# SCH_ZX_WiFi_2022-08-20.net
KiCad netlist of a schematic drawn in EasyEDA
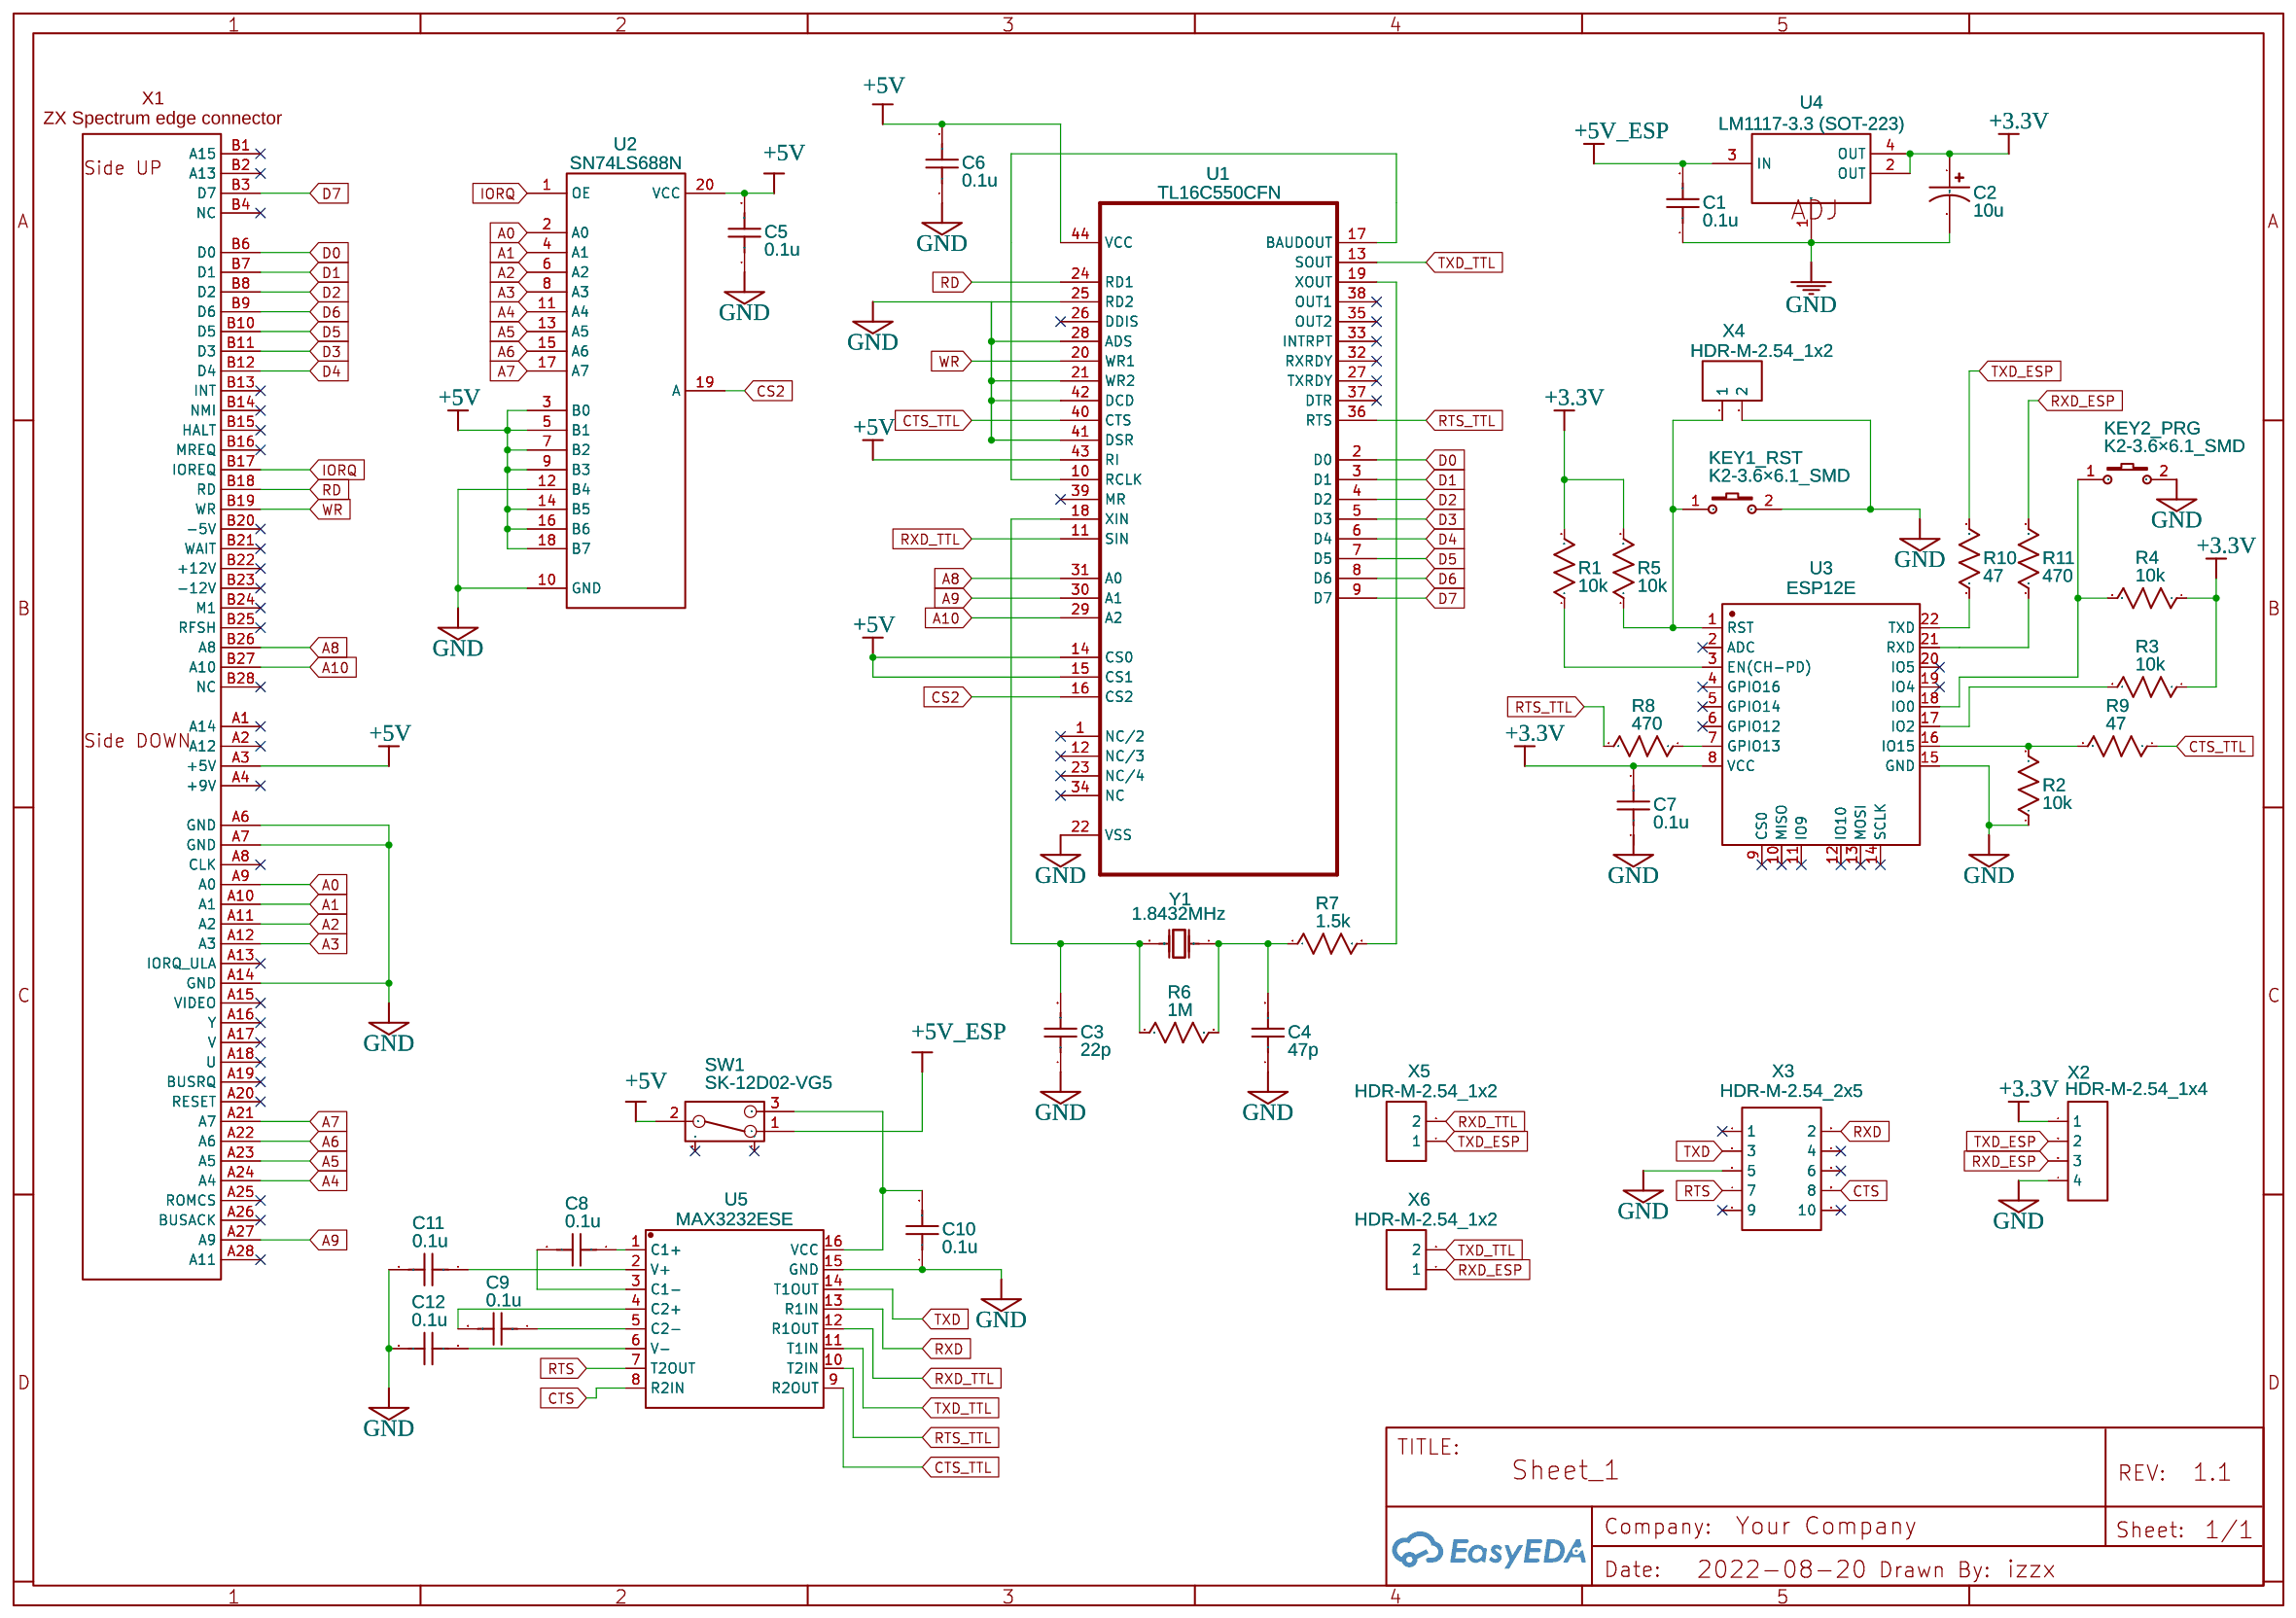
[diagram p0: schematic sheet]

(export (version "E")
  (design (tool "Eeschema 10.0.6"))
  (components
    (comp (ref "C1") (value "0.1u") (libsource (lib "") (part "C_0805_US")))
    (comp (ref "C2") (value "10u") (libsource (lib "") (part "C_Tan_SMD_A_US")))
    (comp (ref "C3") (value "22p") (libsource (lib "") (part "C_0805_US")))
    (comp (ref "C4") (value "47p") (libsource (lib "") (part "C_0805_US")))
    (comp (ref "C5") (value "0.1u") (libsource (lib "") (part "C_0805_US")))
    (comp (ref "C6") (value "0.1u") (libsource (lib "") (part "C_0805_US")))
    (comp (ref "C7") (value "0.1u") (libsource (lib "") (part "C_0805_US")))
    (comp (ref "C8") (value "0.1u") (libsource (lib "") (part "C_0805_US_1")))
    (comp (ref "C9") (value "0.1u") (libsource (lib "") (part "C_0805_US_1")))
    (comp (ref "C10") (value "0.1u") (libsource (lib "") (part "C_0805_US")))
    (comp (ref "C11") (value "0.1u") (libsource (lib "") (part "C_0805_US_1")))
    (comp (ref "C12") (value "0.1u") (libsource (lib "") (part "C_0805_US_1")))
    (comp (ref "KEY1_RST")
      (value "K2-3.6×6.1_SMD")
      (fields
        (field (name "BOM_Manufacturer Part") "K2-1107ST-A4SW-06")
        (field (name "BOM_Supplier Part") "C118141")
      )
      (libsource (lib "") (part "K2-3.6×6.1_SMD_1"))
    )
    (comp (ref "KEY2_PRG")
      (value "K2-3.6×6.1_SMD")
      (fields
        (field (name "BOM_Manufacturer Part") "K2-1107ST-A4SW-06")
        (field (name "BOM_Supplier Part") "C118141")
      )
      (libsource (lib "") (part "K2-3.6×6.1_SMD"))
    )
    (comp (ref "R1") (value "10k") (libsource (lib "") (part "R_0805_US_1")))
    (comp (ref "R2") (value "10k") (libsource (lib "") (part "R_0805_US_1")))
    (comp (ref "R3") (value "10k") (libsource (lib "") (part "R_0805_US_2")))
    (comp (ref "R4") (value "10k") (libsource (lib "") (part "R_0805_US_2")))
    (comp (ref "R5") (value "10k") (libsource (lib "") (part "R_0805_US_1")))
    (comp (ref "R6") (value "1M") (libsource (lib "") (part "R_0805_US")))
    (comp (ref "R7") (value "1.5k") (libsource (lib "") (part "R_0805_US")))
    (comp (ref "R8") (value "470") (libsource (lib "") (part "R_0805_US_2")))
    (comp (ref "R9") (value "47") (libsource (lib "") (part "R_0805_US_2")))
    (comp (ref "R10") (value "47") (libsource (lib "") (part "R_0805_US_1")))
    (comp (ref "R11") (value "470") (libsource (lib "") (part "R_0805_US_1")))
    (comp (ref "SW1")
      (value "SK-12D02-VG5")
      (fields (field (name "BOM_Supplier Part") "C136722"))
      (libsource (lib "") (part "SK-12D02-VG5"))
    )
    (comp (ref "U1") (value "TL16C550CFN") (libsource (lib "") (part "TL16C550CFN")))
    (comp (ref "U2") (value "SN74LS688N") (libsource (lib "") (part "SN74LS688N")))
    (comp (ref "U3") (value "ESP12E") (libsource (lib "") (part "ESP12E/F")))
    (comp (ref "U4")
      (value "LM1117-3.3 (SOT-223)")
      (fields
        (field (name "BOM_Manufacturer Part") "LM317G-AA3-R")
        (field (name "BOM_Supplier Part") "C19651")
      )
      (libsource (lib "") (part "LM317(SOT-223)"))
    )
    (comp (ref "U5")
      (value "MAX3232ESE")
      (fields (field (name "BOM_Supplier Part") "C2904738"))
      (libsource (lib "") (part "MAX3232ESE"))
    )
    (comp (ref "X1") (value "ZX SPECTRUM CONNECTOR") (libsource (lib "") (part "ZX SPECTRUM CONNECTOR")))
    (comp (ref "X2")
      (value "HDR-M-2.54_1x4")
      (fields (field (name "BOM_Supplier Part") "C124378"))
      (libsource (lib "") (part "HDR-M-2.54_1x4"))
    )
    (comp (ref "X3")
      (value "HDR-M-2.54_2x5")
      (fields (field (name "BOM_Supplier Part") "C178292"))
      (libsource (lib "") (part "HDR-M-2.54_2x5"))
    )
    (comp (ref "X4")
      (value "HDR-M-2.54_1x2")
      (fields (field (name "BOM_Supplier Part") "C124375"))
      (libsource (lib "") (part "HDR-M-2.54_1x2_1"))
    )
    (comp (ref "X5")
      (value "HDR-M-2.54_1x2")
      (fields (field (name "BOM_Supplier Part") "C124375"))
      (libsource (lib "") (part "HDR-M-2.54_1x2"))
    )
    (comp (ref "X6")
      (value "HDR-M-2.54_1x2")
      (fields (field (name "BOM_Supplier Part") "C124375"))
      (libsource (lib "") (part "HDR-M-2.54_1x2"))
    )
    (comp (ref "Y1")
      (value "1.8432MHz")
      (fields
        (field (name "BOM_Manufacturer Part") "X49UD3579MSD2SC")
        (field (name "BOM_Supplier Part") "C36564")
      )
      (libsource (lib "") (part "X49UD3579MSD2SC"))
    )
  )
  (nets
    (net (code "1") (name "+3.3V") (class "Default")
      (node (ref "C2") (pin "1") (pinfunction "1_1") (pintype "unspecified"))
      (node (ref "C7") (pin "2") (pinfunction "2_2") (pintype "unspecified"))
      (node (ref "R1") (pin "2") (pinfunction "2_2") (pintype "unspecified"))
      (node (ref "R3") (pin "1") (pinfunction "1_1") (pintype "unspecified"))
      (node (ref "R4") (pin "1") (pinfunction "1_1") (pintype "unspecified"))
      (node (ref "R5") (pin "2") (pinfunction "2_2") (pintype "unspecified"))
      (node (ref "U3") (pin "8") (pinfunction "VCC_8") (pintype "unspecified"))
      (node (ref "U4") (pin "2") (pinfunction "OUT_2") (pintype "passive"))
      (node (ref "U4") (pin "4") (pinfunction "OUT_4") (pintype "passive"))
      (node (ref "X2") (pin "1") (pinfunction "1_1") (pintype "unspecified"))
    )
    (net (code "2") (name "+5V") (class "Default")
      (node (ref "C5") (pin "2") (pinfunction "2_2") (pintype "unspecified"))
      (node (ref "C6") (pin "2") (pinfunction "2_2") (pintype "unspecified"))
      (node (ref "SW1") (pin "2") (pinfunction "2_2") (pintype "unspecified"))
      (node (ref "U1") (pin "14") (pinfunction "CS0_14") (pintype "input"))
      (node (ref "U1") (pin "15") (pinfunction "CS1_15") (pintype "input"))
      (node (ref "U1") (pin "43") (pinfunction "RI_43") (pintype "input"))
      (node (ref "U1") (pin "44") (pinfunction "VCC_44") (pintype "passive"))
      (node (ref "U2") (pin "14") (pinfunction "B5_14") (pintype "unspecified"))
      (node (ref "U2") (pin "16") (pinfunction "B6_16") (pintype "unspecified"))
      (node (ref "U2") (pin "18") (pinfunction "B7_18") (pintype "unspecified"))
      (node (ref "U2") (pin "20") (pinfunction "VCC_20") (pintype "passive"))
      (node (ref "U2") (pin "3") (pinfunction "B0_3") (pintype "unspecified"))
      (node (ref "U2") (pin "5") (pinfunction "B1_5") (pintype "unspecified"))
      (node (ref "U2") (pin "7") (pinfunction "B2_7") (pintype "unspecified"))
      (node (ref "U2") (pin "9") (pinfunction "B3_9") (pintype "unspecified"))
      (node (ref "X1") (pin "A3") (pinfunction "+5V_A3") (pintype "unspecified"))
    )
    (net (code "3") (name "+5V_ESP") (class "Default")
      (node (ref "C1") (pin "2") (pinfunction "2_2") (pintype "unspecified"))
      (node (ref "SW1") (pin "1") (pinfunction "1_1") (pintype "unspecified"))
      (node (ref "U4") (pin "3") (pinfunction "IN_3") (pintype "passive"))
    )
    (net (code "4") (name "A0") (class "Default")
      (node (ref "U2") (pin "2") (pinfunction "A0_2") (pintype "unspecified"))
      (node (ref "X1") (pin "A9") (pinfunction "A0_A9") (pintype "unspecified"))
    )
    (net (code "5") (name "A1") (class "Default")
      (node (ref "U2") (pin "4") (pinfunction "A1_4") (pintype "unspecified"))
      (node (ref "X1") (pin "A10") (pinfunction "A1_A10") (pintype "unspecified"))
    )
    (net (code "6") (name "A2") (class "Default")
      (node (ref "U2") (pin "6") (pinfunction "A2_6") (pintype "unspecified"))
      (node (ref "X1") (pin "A11") (pinfunction "A2_A11") (pintype "unspecified"))
    )
    (net (code "7") (name "A3") (class "Default")
      (node (ref "U2") (pin "8") (pinfunction "A3_8") (pintype "unspecified"))
      (node (ref "X1") (pin "A12") (pinfunction "A3_A12") (pintype "unspecified"))
    )
    (net (code "8") (name "A4") (class "Default")
      (node (ref "U2") (pin "11") (pinfunction "A4_11") (pintype "unspecified"))
      (node (ref "X1") (pin "A24") (pinfunction "A4_A24") (pintype "unspecified"))
    )
    (net (code "9") (name "A5") (class "Default")
      (node (ref "U2") (pin "13") (pinfunction "A5_13") (pintype "unspecified"))
      (node (ref "X1") (pin "A23") (pinfunction "A5_A23") (pintype "unspecified"))
    )
    (net (code "10") (name "A6") (class "Default")
      (node (ref "U2") (pin "15") (pinfunction "A6_15") (pintype "unspecified"))
      (node (ref "X1") (pin "A22") (pinfunction "A6_A22") (pintype "unspecified"))
    )
    (net (code "11") (name "A7") (class "Default")
      (node (ref "U2") (pin "17") (pinfunction "A7_17") (pintype "unspecified"))
      (node (ref "X1") (pin "A21") (pinfunction "A7_A21") (pintype "unspecified"))
    )
    (net (code "12") (name "A8") (class "Default")
      (node (ref "U1") (pin "31") (pinfunction "A0_31") (pintype "input"))
      (node (ref "X1") (pin "B26") (pinfunction "A8_B26") (pintype "unspecified"))
    )
    (net (code "13") (name "A9") (class "Default")
      (node (ref "U1") (pin "30") (pinfunction "A1_30") (pintype "input"))
      (node (ref "X1") (pin "A27") (pinfunction "A9_A27") (pintype "unspecified"))
    )
    (net (code "14") (name "A10") (class "Default")
      (node (ref "U1") (pin "29") (pinfunction "A2_29") (pintype "input"))
      (node (ref "X1") (pin "B27") (pinfunction "A10_B27") (pintype "unspecified"))
    )
    (net (code "15") (name "CS2") (class "Default")
      (node (ref "U1") (pin "16") (pinfunction "CS2_16") (pintype "input"))
      (node (ref "U2") (pin "19") (pinfunction "A_19") (pintype "output"))
    )
    (net (code "16") (name "CTS") (class "Default")
      (node (ref "U5") (pin "8") (pinfunction "R2IN_8") (pintype "unspecified"))
      (node (ref "X3") (pin "8") (pinfunction "8_8") (pintype "unspecified"))
    )
    (net (code "17") (name "CTS_TTL") (class "Default")
      (node (ref "R9") (pin "1") (pinfunction "1_1") (pintype "unspecified"))
      (node (ref "U1") (pin "40") (pinfunction "CTS_40") (pintype "input"))
      (node (ref "U5") (pin "9") (pinfunction "R2OUT_9") (pintype "unspecified"))
    )
    (net (code "18") (name "D0") (class "Default")
      (node (ref "U1") (pin "2") (pinfunction "D0_2") (pintype "unspecified"))
      (node (ref "X1") (pin "B6") (pinfunction "D0_B6") (pintype "bidirectional"))
    )
    (net (code "19") (name "D1") (class "Default")
      (node (ref "U1") (pin "3") (pinfunction "D1_3") (pintype "unspecified"))
      (node (ref "X1") (pin "B7") (pinfunction "D1_B7") (pintype "bidirectional"))
    )
    (net (code "20") (name "D2") (class "Default")
      (node (ref "U1") (pin "4") (pinfunction "D2_4") (pintype "unspecified"))
      (node (ref "X1") (pin "B8") (pinfunction "D2_B8") (pintype "bidirectional"))
    )
    (net (code "21") (name "D3") (class "Default")
      (node (ref "U1") (pin "5") (pinfunction "D3_5") (pintype "unspecified"))
      (node (ref "X1") (pin "B11") (pinfunction "D3_B11") (pintype "unspecified"))
    )
    (net (code "22") (name "D4") (class "Default")
      (node (ref "U1") (pin "6") (pinfunction "D4_6") (pintype "unspecified"))
      (node (ref "X1") (pin "B12") (pinfunction "D4_B12") (pintype "unspecified"))
    )
    (net (code "23") (name "D5") (class "Default")
      (node (ref "U1") (pin "7") (pinfunction "D5_7") (pintype "unspecified"))
      (node (ref "X1") (pin "B10") (pinfunction "D5_B10") (pintype "bidirectional"))
    )
    (net (code "24") (name "D6") (class "Default")
      (node (ref "U1") (pin "8") (pinfunction "D6_8") (pintype "unspecified"))
      (node (ref "X1") (pin "B9") (pinfunction "D6_B9") (pintype "unspecified"))
    )
    (net (code "25") (name "D7") (class "Default")
      (node (ref "U1") (pin "9") (pinfunction "D7_9") (pintype "unspecified"))
      (node (ref "X1") (pin "B3") (pinfunction "D7_B3") (pintype "bidirectional"))
    )
    (net (code "26") (name "GND") (class "Default")
      (node (ref "C1") (pin "1") (pinfunction "1_1") (pintype "unspecified"))
      (node (ref "C10") (pin "1") (pinfunction "1_1") (pintype "unspecified"))
      (node (ref "C11") (pin "2") (pinfunction "2_2") (pintype "unspecified"))
      (node (ref "C12") (pin "2") (pinfunction "2_2") (pintype "unspecified"))
      (node (ref "C2") (pin "2") (pinfunction "2_2") (pintype "unspecified"))
      (node (ref "C3") (pin "1") (pinfunction "1_1") (pintype "unspecified"))
      (node (ref "C4") (pin "1") (pinfunction "1_1") (pintype "unspecified"))
      (node (ref "C5") (pin "1") (pinfunction "1_1") (pintype "unspecified"))
      (node (ref "C6") (pin "1") (pinfunction "1_1") (pintype "unspecified"))
      (node (ref "C7") (pin "1") (pinfunction "1_1") (pintype "unspecified"))
      (node (ref "KEY1_RST") (pin "2") (pinfunction "2_2") (pintype "unspecified"))
      (node (ref "KEY2_PRG") (pin "2") (pinfunction "2_2") (pintype "unspecified"))
      (node (ref "R2") (pin "1") (pinfunction "1_1") (pintype "unspecified"))
      (node (ref "U1") (pin "21") (pinfunction "WR2_21") (pintype "input"))
      (node (ref "U1") (pin "22") (pinfunction "VSS_22") (pintype "passive"))
      (node (ref "U1") (pin "25") (pinfunction "RD2_25") (pintype "input"))
      (node (ref "U1") (pin "28") (pinfunction "ADS_28") (pintype "input"))
      (node (ref "U1") (pin "41") (pinfunction "DSR_41") (pintype "input"))
      (node (ref "U1") (pin "42") (pinfunction "DCD_42") (pintype "input"))
      (node (ref "U2") (pin "10") (pinfunction "GND_10") (pintype "passive"))
      (node (ref "U2") (pin "12") (pinfunction "B4_12") (pintype "unspecified"))
      (node (ref "U3") (pin "15") (pinfunction "GND_15") (pintype "unspecified"))
      (node (ref "U4") (pin "1") (pinfunction "ADJ_1") (pintype "passive"))
      (node (ref "U5") (pin "15") (pinfunction "GND_15") (pintype "unspecified"))
      (node (ref "X1") (pin "A14") (pinfunction "GND_A14") (pintype "unspecified"))
      (node (ref "X1") (pin "A6") (pinfunction "GND_A6") (pintype "unspecified"))
      (node (ref "X1") (pin "A7") (pinfunction "GND_A7") (pintype "unspecified"))
      (node (ref "X2") (pin "4") (pinfunction "4_4") (pintype "unspecified"))
      (node (ref "X3") (pin "5") (pinfunction "5_5") (pintype "unspecified"))
      (node (ref "X4") (pin "2") (pinfunction "2_2") (pintype "unspecified"))
    )
    (net (code "27") (name "IORQ") (class "Default")
      (node (ref "U2") (pin "1") (pinfunction "OE_1") (pintype "unspecified"))
      (node (ref "X1") (pin "B17") (pinfunction "IOREQ_B17") (pintype "unspecified"))
    )
    (net (code "28") (name "Net-(U1-BAUDOUT)") (class "Default")
      (node (ref "U1") (pin "10") (pinfunction "RCLK_10") (pintype "input"))
      (node (ref "U1") (pin "17") (pinfunction "BAUDOUT_17") (pintype "output"))
    )
    (net (code "29") (name "Net-(U1-XIN)") (class "Default")
      (node (ref "C3") (pin "2") (pinfunction "2_2") (pintype "unspecified"))
      (node (ref "R6") (pin "1") (pinfunction "1_1") (pintype "unspecified"))
      (node (ref "U1") (pin "18") (pinfunction "XIN_18") (pintype "input"))
      (node (ref "Y1") (pin "2") (pinfunction "OSC2_2") (pintype "input"))
    )
    (net (code "30") (name "Net-(U1-XOUT)") (class "Default")
      (node (ref "R7") (pin "2") (pinfunction "2_2") (pintype "unspecified"))
      (node (ref "U1") (pin "19") (pinfunction "XOUT_19") (pintype "output"))
    )
    (net (code "31") (name "Net-(U3-EN(CH-PD))") (class "Default")
      (node (ref "R1") (pin "1") (pinfunction "1_1") (pintype "unspecified"))
      (node (ref "U3") (pin "3") (pinfunction "EN(CH-PD)_3") (pintype "unspecified"))
    )
    (net (code "32") (name "Net-(U3-GPIO13)") (class "Default")
      (node (ref "R8") (pin "1") (pinfunction "1_1") (pintype "unspecified"))
      (node (ref "U3") (pin "7") (pinfunction "GPIO13_7") (pintype "unspecified"))
    )
    (net (code "33") (name "Net-(U3-IO0)") (class "Default")
      (node (ref "KEY2_PRG") (pin "1") (pinfunction "1_1") (pintype "unspecified"))
      (node (ref "R4") (pin "2") (pinfunction "2_2") (pintype "unspecified"))
      (node (ref "U3") (pin "18") (pinfunction "IO0_18") (pintype "unspecified"))
    )
    (net (code "34") (name "Net-(U3-IO2)") (class "Default")
      (node (ref "R3") (pin "2") (pinfunction "2_2") (pintype "unspecified"))
      (node (ref "U3") (pin "17") (pinfunction "IO2_17") (pintype "unspecified"))
    )
    (net (code "35") (name "Net-(U3-IO15)") (class "Default")
      (node (ref "R2") (pin "2") (pinfunction "2_2") (pintype "unspecified"))
      (node (ref "R9") (pin "2") (pinfunction "2_2") (pintype "unspecified"))
      (node (ref "U3") (pin "16") (pinfunction "IO15_16") (pintype "unspecified"))
    )
    (net (code "36") (name "Net-(U3-RST)") (class "Default")
      (node (ref "KEY1_RST") (pin "1") (pinfunction "1_1") (pintype "unspecified"))
      (node (ref "R5") (pin "1") (pinfunction "1_1") (pintype "unspecified"))
      (node (ref "U3") (pin "1") (pinfunction "RST_1") (pintype "unspecified"))
      (node (ref "X4") (pin "1") (pinfunction "1_1") (pintype "unspecified"))
    )
    (net (code "37") (name "Net-(U3-RXD)") (class "Default")
      (node (ref "R11") (pin "1") (pinfunction "1_1") (pintype "unspecified"))
      (node (ref "U3") (pin "21") (pinfunction "RXD_21") (pintype "unspecified"))
    )
    (net (code "38") (name "Net-(U3-TXD)") (class "Default")
      (node (ref "R10") (pin "1") (pinfunction "1_1") (pintype "unspecified"))
      (node (ref "U3") (pin "22") (pinfunction "TXD_22") (pintype "unspecified"))
    )
    (net (code "39") (name "Net-(U5-C1+)") (class "Default")
      (node (ref "C8") (pin "1") (pinfunction "1_1") (pintype "unspecified"))
      (node (ref "U5") (pin "1") (pinfunction "C1+_1") (pintype "unspecified"))
    )
    (net (code "40") (name "Net-(U5-C1-)") (class "Default")
      (node (ref "C8") (pin "2") (pinfunction "2_2") (pintype "unspecified"))
      (node (ref "U5") (pin "3") (pinfunction "C1-_3") (pintype "unspecified"))
    )
    (net (code "41") (name "Net-(U5-C2+)") (class "Default")
      (node (ref "C9") (pin "2") (pinfunction "2_2") (pintype "unspecified"))
      (node (ref "U5") (pin "4") (pinfunction "C2+_4") (pintype "unspecified"))
    )
    (net (code "42") (name "Net-(U5-C2-)") (class "Default")
      (node (ref "C9") (pin "1") (pinfunction "1_1") (pintype "unspecified"))
      (node (ref "U5") (pin "5") (pinfunction "C2-_5") (pintype "unspecified"))
    )
    (net (code "43") (name "Net-(U5-V+)") (class "Default")
      (node (ref "C11") (pin "1") (pinfunction "1_1") (pintype "unspecified"))
      (node (ref "U5") (pin "2") (pinfunction "V+_2") (pintype "unspecified"))
    )
    (net (code "44") (name "Net-(U5-V-)") (class "Default")
      (node (ref "C12") (pin "1") (pinfunction "1_1") (pintype "unspecified"))
      (node (ref "U5") (pin "6") (pinfunction "V-_6") (pintype "unspecified"))
    )
    (net (code "45") (name "Net-(U5-VCC)") (class "Default")
      (node (ref "C10") (pin "2") (pinfunction "2_2") (pintype "unspecified"))
      (node (ref "SW1") (pin "3") (pinfunction "3_3") (pintype "unspecified"))
      (node (ref "U5") (pin "16") (pinfunction "VCC_16") (pintype "unspecified"))
    )
    (net (code "46") (name "Net-(Y1-OSC1)") (class "Default")
      (node (ref "C4") (pin "2") (pinfunction "2_2") (pintype "unspecified"))
      (node (ref "R6") (pin "2") (pinfunction "2_2") (pintype "unspecified"))
      (node (ref "R7") (pin "1") (pinfunction "1_1") (pintype "unspecified"))
      (node (ref "Y1") (pin "1") (pinfunction "OSC1_1") (pintype "input"))
    )
    (net (code "47") (name "RD") (class "Default")
      (node (ref "U1") (pin "24") (pinfunction "RD1_24") (pintype "input"))
      (node (ref "X1") (pin "B18") (pinfunction "RD_B18") (pintype "unspecified"))
    )
    (net (code "48") (name "RTS") (class "Default")
      (node (ref "U5") (pin "7") (pinfunction "T2OUT_7") (pintype "unspecified"))
      (node (ref "X3") (pin "7") (pinfunction "7_7") (pintype "unspecified"))
    )
    (net (code "49") (name "RTS_TTL") (class "Default")
      (node (ref "R8") (pin "2") (pinfunction "2_2") (pintype "unspecified"))
      (node (ref "U1") (pin "36") (pinfunction "RTS_36") (pintype "output"))
      (node (ref "U5") (pin "10") (pinfunction "T2IN_10") (pintype "unspecified"))
    )
    (net (code "50") (name "RXD") (class "Default")
      (node (ref "U5") (pin "13") (pinfunction "R1IN_13") (pintype "unspecified"))
      (node (ref "X3") (pin "2") (pinfunction "2_2") (pintype "unspecified"))
    )
    (net (code "51") (name "RXD_ESP") (class "Default")
      (node (ref "R11") (pin "2") (pinfunction "2_2") (pintype "unspecified"))
      (node (ref "X2") (pin "3") (pinfunction "3_3") (pintype "unspecified"))
      (node (ref "X6") (pin "1") (pinfunction "1_1") (pintype "unspecified"))
    )
    (net (code "52") (name "RXD_TTL") (class "Default")
      (node (ref "U1") (pin "11") (pinfunction "SIN_11") (pintype "input"))
      (node (ref "U5") (pin "12") (pinfunction "R1OUT_12") (pintype "unspecified"))
      (node (ref "X5") (pin "2") (pinfunction "2_2") (pintype "unspecified"))
    )
    (net (code "53") (name "TXD") (class "Default")
      (node (ref "U5") (pin "14") (pinfunction "T1OUT_14") (pintype "unspecified"))
      (node (ref "X3") (pin "3") (pinfunction "3_3") (pintype "unspecified"))
    )
    (net (code "54") (name "TXD_ESP") (class "Default")
      (node (ref "R10") (pin "2") (pinfunction "2_2") (pintype "unspecified"))
      (node (ref "X2") (pin "2") (pinfunction "2_2") (pintype "unspecified"))
      (node (ref "X5") (pin "1") (pinfunction "1_1") (pintype "unspecified"))
    )
    (net (code "55") (name "TXD_TTL") (class "Default")
      (node (ref "U1") (pin "13") (pinfunction "SOUT_13") (pintype "output"))
      (node (ref "U5") (pin "11") (pinfunction "T1IN_11") (pintype "unspecified"))
      (node (ref "X6") (pin "2") (pinfunction "2_2") (pintype "unspecified"))
    )
    (net (code "56") (name "WR") (class "Default")
      (node (ref "U1") (pin "20") (pinfunction "WR1_20") (pintype "input"))
      (node (ref "X1") (pin "B19") (pinfunction "WR_B19") (pintype "unspecified"))
    )
    (net (code "57") (name "unconnected-(SW1-Pad4)") (class "Default")
      (node (ref "SW1") (pin "4") (pinfunction "4_4") (pintype "unspecified+no_connect"))
    )
    (net (code "58") (name "unconnected-(SW1-Pad5)") (class "Default")
      (node (ref "SW1") (pin "5") (pinfunction "5_5") (pintype "unspecified+no_connect"))
    )
    (net (code "59") (name "unconnected-(U1-DDIS-Pad26)") (class "Default")
      (node (ref "U1") (pin "26") (pinfunction "DDIS_26") (pintype "input+no_connect"))
    )
    (net (code "60") (name "unconnected-(U1-DTR-Pad37)") (class "Default")
      (node (ref "U1") (pin "37") (pinfunction "DTR_37") (pintype "output+no_connect"))
    )
    (net (code "61") (name "unconnected-(U1-INTRPT-Pad33)") (class "Default")
      (node (ref "U1") (pin "33") (pinfunction "INTRPT_33") (pintype "output+no_connect"))
    )
    (net (code "62") (name "unconnected-(U1-MR-Pad39)") (class "Default")
      (node (ref "U1") (pin "39") (pinfunction "MR_39") (pintype "input+no_connect"))
    )
    (net (code "63") (name "unconnected-(U1-NC-Pad34)") (class "Default")
      (node (ref "U1") (pin "34") (pinfunction "NC_34") (pintype "unspecified+no_connect"))
    )
    (net (code "64") (name "unconnected-(U1-NC{slash}2-Pad1)") (class "Default")
      (node (ref "U1") (pin "1") (pinfunction "NC/2_1") (pintype "unspecified+no_connect"))
    )
    (net (code "65") (name "unconnected-(U1-NC{slash}3-Pad12)") (class "Default")
      (node (ref "U1") (pin "12") (pinfunction "NC/3_12") (pintype "unspecified+no_connect"))
    )
    (net (code "66") (name "unconnected-(U1-NC{slash}4-Pad23)") (class "Default")
      (node (ref "U1") (pin "23") (pinfunction "NC/4_23") (pintype "unspecified+no_connect"))
    )
    (net (code "67") (name "unconnected-(U1-OUT1-Pad38)") (class "Default")
      (node (ref "U1") (pin "38") (pinfunction "OUT1_38") (pintype "output+no_connect"))
    )
    (net (code "68") (name "unconnected-(U1-OUT2-Pad35)") (class "Default")
      (node (ref "U1") (pin "35") (pinfunction "OUT2_35") (pintype "output+no_connect"))
    )
    (net (code "69") (name "unconnected-(U1-RXRDY-Pad32)") (class "Default")
      (node (ref "U1") (pin "32") (pinfunction "RXRDY_32") (pintype "output+no_connect"))
    )
    (net (code "70") (name "unconnected-(U1-TXRDY-Pad27)") (class "Default")
      (node (ref "U1") (pin "27") (pinfunction "TXRDY_27") (pintype "output+no_connect"))
    )
    (net (code "71") (name "unconnected-(U3-ADC-Pad2)") (class "Default")
      (node (ref "U3") (pin "2") (pinfunction "ADC_2") (pintype "unspecified+no_connect"))
    )
    (net (code "72") (name "unconnected-(U3-CS0-Pad9)") (class "Default")
      (node (ref "U3") (pin "9") (pinfunction "CS0_9") (pintype "unspecified+no_connect"))
    )
    (net (code "73") (name "unconnected-(U3-GPIO12-Pad6)") (class "Default")
      (node (ref "U3") (pin "6") (pinfunction "GPIO12_6") (pintype "unspecified+no_connect"))
    )
    (net (code "74") (name "unconnected-(U3-GPIO14-Pad5)") (class "Default")
      (node (ref "U3") (pin "5") (pinfunction "GPIO14_5") (pintype "unspecified+no_connect"))
    )
    (net (code "75") (name "unconnected-(U3-GPIO16-Pad4)") (class "Default")
      (node (ref "U3") (pin "4") (pinfunction "GPIO16_4") (pintype "unspecified+no_connect"))
    )
    (net (code "76") (name "unconnected-(U3-IO4-Pad19)") (class "Default")
      (node (ref "U3") (pin "19") (pinfunction "IO4_19") (pintype "unspecified+no_connect"))
    )
    (net (code "77") (name "unconnected-(U3-IO5-Pad20)") (class "Default")
      (node (ref "U3") (pin "20") (pinfunction "IO5_20") (pintype "unspecified+no_connect"))
    )
    (net (code "78") (name "unconnected-(U3-IO9-Pad11)") (class "Default")
      (node (ref "U3") (pin "11") (pinfunction "IO9_11") (pintype "unspecified+no_connect"))
    )
    (net (code "79") (name "unconnected-(U3-IO10-Pad12)") (class "Default")
      (node (ref "U3") (pin "12") (pinfunction "IO10_12") (pintype "unspecified+no_connect"))
    )
    (net (code "80") (name "unconnected-(U3-MISO-Pad10)") (class "Default")
      (node (ref "U3") (pin "10") (pinfunction "MISO_10") (pintype "unspecified+no_connect"))
    )
    (net (code "81") (name "unconnected-(U3-MOSI-Pad13)") (class "Default")
      (node (ref "U3") (pin "13") (pinfunction "MOSI_13") (pintype "unspecified+no_connect"))
    )
    (net (code "82") (name "unconnected-(U3-SCLK-Pad14)") (class "Default")
      (node (ref "U3") (pin "14") (pinfunction "SCLK_14") (pintype "unspecified+no_connect"))
    )
    (net (code "83") (name "unconnected-(X1-+9V-PadA4)") (class "Default")
      (node (ref "X1") (pin "A4") (pinfunction "+9V_A4") (pintype "unspecified+no_connect"))
    )
    (net (code "84") (name "unconnected-(X1-+12V-PadB22)") (class "Default")
      (node (ref "X1") (pin "B22") (pinfunction "+12V_B22") (pintype "unspecified+no_connect"))
    )
    (net (code "85") (name "unconnected-(X1--5V-PadB20)") (class "Default")
      (node (ref "X1") (pin "B20") (pinfunction "-5V_B20") (pintype "unspecified+no_connect"))
    )
    (net (code "86") (name "unconnected-(X1--12V-PadB23)") (class "Default")
      (node (ref "X1") (pin "B23") (pinfunction "-12V_B23") (pintype "unspecified+no_connect"))
    )
    (net (code "87") (name "unconnected-(X1-A11-PadA28)") (class "Default")
      (node (ref "X1") (pin "A28") (pinfunction "A11_A28") (pintype "unspecified+no_connect"))
    )
    (net (code "88") (name "unconnected-(X1-A12-PadA2)") (class "Default")
      (node (ref "X1") (pin "A2") (pinfunction "A12_A2") (pintype "unspecified+no_connect"))
    )
    (net (code "89") (name "unconnected-(X1-A13-PadB2)") (class "Default")
      (node (ref "X1") (pin "B2") (pinfunction "A13_B2") (pintype "output+no_connect"))
    )
    (net (code "90") (name "unconnected-(X1-A14-PadA1)") (class "Default")
      (node (ref "X1") (pin "A1") (pinfunction "A14_A1") (pintype "unspecified+no_connect"))
    )
    (net (code "91") (name "unconnected-(X1-A15-PadB1)") (class "Default")
      (node (ref "X1") (pin "B1") (pinfunction "A15_B1") (pintype "output+no_connect"))
    )
    (net (code "92") (name "unconnected-(X1-BUSACK-PadA26)") (class "Default")
      (node (ref "X1") (pin "A26") (pinfunction "BUSACK_A26") (pintype "unspecified+no_connect"))
    )
    (net (code "93") (name "unconnected-(X1-BUSRQ-PadA19)") (class "Default")
      (node (ref "X1") (pin "A19") (pinfunction "BUSRQ_A19") (pintype "unspecified+no_connect"))
    )
    (net (code "94") (name "unconnected-(X1-CLK-PadA8)") (class "Default")
      (node (ref "X1") (pin "A8") (pinfunction "CLK_A8") (pintype "unspecified+no_connect"))
    )
    (net (code "95") (name "unconnected-(X1-HALT-PadB15)") (class "Default")
      (node (ref "X1") (pin "B15") (pinfunction "HALT_B15") (pintype "unspecified+no_connect"))
    )
    (net (code "96") (name "unconnected-(X1-INT-PadB13)") (class "Default")
      (node (ref "X1") (pin "B13") (pinfunction "INT_B13") (pintype "unspecified+no_connect"))
    )
    (net (code "97") (name "unconnected-(X1-IORQ_ULA-PadA13)") (class "Default")
      (node (ref "X1") (pin "A13") (pinfunction "IORQ_ULA_A13") (pintype "unspecified+no_connect"))
    )
    (net (code "98") (name "unconnected-(X1-M1-PadB24)") (class "Default")
      (node (ref "X1") (pin "B24") (pinfunction "M1_B24") (pintype "unspecified+no_connect"))
    )
    (net (code "99") (name "unconnected-(X1-MREQ-PadB16)") (class "Default")
      (node (ref "X1") (pin "B16") (pinfunction "MREQ_B16") (pintype "unspecified+no_connect"))
    )
    (net (code "100") (name "unconnected-(X1-NC-PadB4)") (class "Default")
      (node (ref "X1") (pin "B4") (pinfunction "NC_B4") (pintype "unspecified+no_connect"))
    )
    (net (code "101") (name "unconnected-(X1-NC-PadB28)") (class "Default")
      (node (ref "X1") (pin "B28") (pinfunction "NC_B28") (pintype "unspecified+no_connect"))
    )
    (net (code "102") (name "unconnected-(X1-NMI-PadB14)") (class "Default")
      (node (ref "X1") (pin "B14") (pinfunction "NMI_B14") (pintype "unspecified+no_connect"))
    )
    (net (code "103") (name "unconnected-(X1-RESET-PadA20)") (class "Default")
      (node (ref "X1") (pin "A20") (pinfunction "RESET_A20") (pintype "unspecified+no_connect"))
    )
    (net (code "104") (name "unconnected-(X1-RFSH-PadB25)") (class "Default")
      (node (ref "X1") (pin "B25") (pinfunction "RFSH_B25") (pintype "unspecified+no_connect"))
    )
    (net (code "105") (name "unconnected-(X1-ROMCS-PadA25)") (class "Default")
      (node (ref "X1") (pin "A25") (pinfunction "ROMCS_A25") (pintype "unspecified+no_connect"))
    )
    (net (code "106") (name "unconnected-(X1-U-PadA18)") (class "Default")
      (node (ref "X1") (pin "A18") (pinfunction "U_A18") (pintype "unspecified+no_connect"))
    )
    (net (code "107") (name "unconnected-(X1-V-PadA17)") (class "Default")
      (node (ref "X1") (pin "A17") (pinfunction "V_A17") (pintype "unspecified+no_connect"))
    )
    (net (code "108") (name "unconnected-(X1-VIDEO-PadA15)") (class "Default")
      (node (ref "X1") (pin "A15") (pinfunction "VIDEO_A15") (pintype "unspecified+no_connect"))
    )
    (net (code "109") (name "unconnected-(X1-WAIT-PadB21)") (class "Default")
      (node (ref "X1") (pin "B21") (pinfunction "WAIT_B21") (pintype "unspecified+no_connect"))
    )
    (net (code "110") (name "unconnected-(X1-Y-PadA16)") (class "Default")
      (node (ref "X1") (pin "A16") (pinfunction "Y_A16") (pintype "unspecified+no_connect"))
    )
    (net (code "111") (name "unconnected-(X3-Pad1)") (class "Default")
      (node (ref "X3") (pin "1") (pinfunction "1_1") (pintype "unspecified+no_connect"))
    )
    (net (code "112") (name "unconnected-(X3-Pad4)") (class "Default")
      (node (ref "X3") (pin "4") (pinfunction "4_4") (pintype "unspecified+no_connect"))
    )
    (net (code "113") (name "unconnected-(X3-Pad6)") (class "Default")
      (node (ref "X3") (pin "6") (pinfunction "6_6") (pintype "unspecified+no_connect"))
    )
    (net (code "114") (name "unconnected-(X3-Pad9)") (class "Default")
      (node (ref "X3") (pin "9") (pinfunction "9_9") (pintype "unspecified+no_connect"))
    )
    (net (code "115") (name "unconnected-(X3-Pad10)") (class "Default")
      (node (ref "X3") (pin "10") (pinfunction "10_10") (pintype "unspecified+no_connect"))
    )
  )
)
